# PowerHAT_1B1.net
KiCad netlist of a schematic drawn in Altium Designer
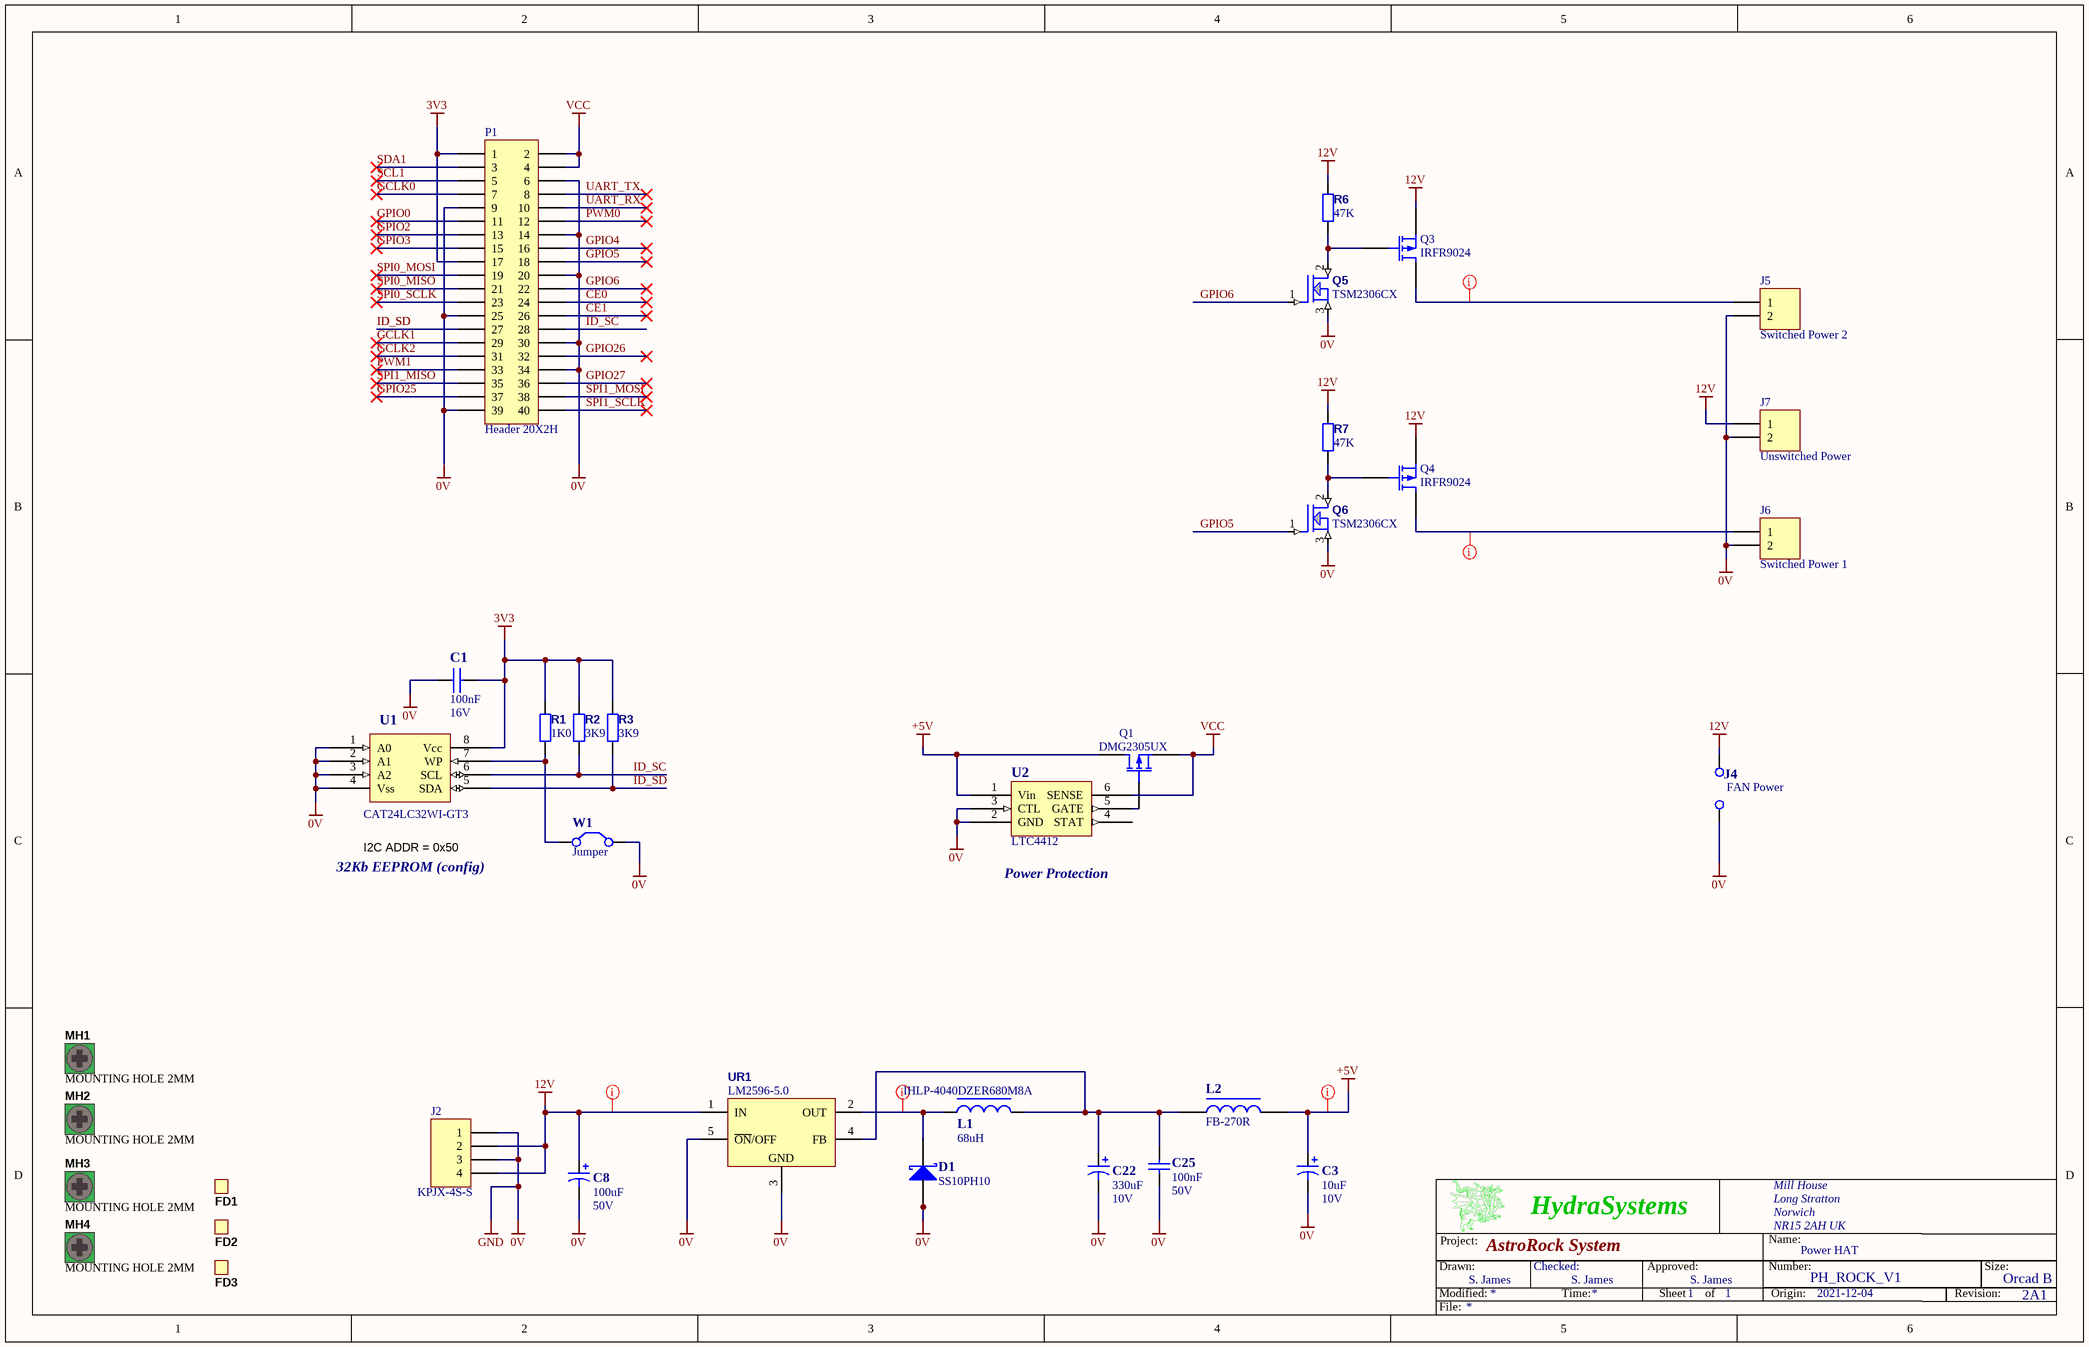
[diagram p0: PowerHAT_1B1.SchDoc]

(export (version "E")
  (design (tool "Eeschema 10.0.6"))
  (components
    (comp (ref "C1")
      (value "100nF")
      (footprint "0603_C")
      (description "MLCC 100nF 0402 X7R 16V")
      (fields (field (name "VOLTAGE") "16V"))
      (libsource (lib "*") (part "CAPACITOR NON-POL"))
    )
    (comp (ref "C3")
      (value "10uF")
      (footprint "1206")
      (description "Polarized Capacitor (Surface Mount)")
      (fields (field (name "VOLTAGE") "10V"))
      (libsource (lib "Miscellaneous Devices") (part "Cap Pol3"))
    )
    (comp (ref "C8")
      (value "100uF")
      (footprint "CASE H")
      (description "Polarized Capacitor (Surface Mount)")
      (fields (field (name "VOLTAGE") "50V"))
      (libsource (lib "Miscellaneous Devices") (part "Cap Pol3"))
    )
    (comp (ref "C22")
      (value "330uF")
      (footprint "2812")
      (description "Polarized Capacitor (Surface Mount)")
      (fields (field (name "VOLTAGE") "10V"))
      (libsource (lib "Miscellaneous Devices") (part "Cap Pol3"))
    )
    (comp (ref "C25")
      (value "100nF")
      (footprint "SM/R_0603")
      (description "Capacitor")
      (fields (field (name "VOLTAGE") "50V"))
      (libsource (lib "A1267-1A1") (part "Cap"))
    )
    (comp (ref "D1")
      (value "SS10PH10")
      (footprint "TO-277A")
      (description "Schottky Rectifier")
      (fields (field (name "MANUFACTURER") "Vishay"))
      (libsource (lib "BoatMonitor_2A1") (part "SS10PH"))
    )
    (comp (ref "FD1")
      (value "Fiducial")
      (footprint "Fiducial")
      (description "Registration Fiducial")
      (libsource (lib "Fiducial_1A1") (part "Fiducial"))
    )
    (comp (ref "FD2")
      (value "Fiducial")
      (footprint "Fiducial")
      (description "Registration Fiducial")
      (libsource (lib "Fiducial_1A1") (part "Fiducial"))
    )
    (comp (ref "FD3")
      (value "Fiducial")
      (footprint "Fiducial")
      (description "Registration Fiducial")
      (libsource (lib "Fiducial_1A1") (part "Fiducial"))
    )
    (comp (ref "J2")
      (value "KPJX-4S-S")
      (footprint "KPJX-4S-S")
      (description "Power 4-Pin")
      (fields (field (name "PUBLISHER") "Altium Limited"))
      (libsource (lib "Miscellaneous Connectors") (part "Header 4"))
    )
    (comp (ref "J4")
      (value "FAN Power")
      (footprint "CON2")
      (description "2 pads")
      (fields (field (name "PUBLISHER") "Altium Limited"))
      (libsource (lib "PowerHAT_1A1") (part "Pads"))
    )
    (comp (ref "J5")
      (value "Switched Power 2")
      (footprint "DCJ250-20")
      (description "Power Jack")
      (fields (field (name "PUBLISHER") "Altium Limited"))
      (libsource (lib "Miscellaneous Connectors") (part "Header 2"))
    )
    (comp (ref "J6")
      (value "Switched Power 1")
      (footprint "DCJ250-20")
      (description "Power Jack")
      (fields (field (name "PUBLISHER") "Altium Limited"))
      (libsource (lib "Miscellaneous Connectors") (part "Header 2"))
    )
    (comp (ref "J7")
      (value "Unswitched Power")
      (footprint "DCJ250-20")
      (description "Power Jack")
      (fields (field (name "PUBLISHER") "Altium Limited"))
      (libsource (lib "Miscellaneous Connectors") (part "Header 2"))
    )
    (comp (ref "L1")
      (value "68uH")
      (footprint "IHLP4040DZER")
      (description "Ferrite Inductor")
      (fields (field (name "MANUFACTURER") "Vishay") (field (name "PART NUMBER 68") "IHLP-4040DZER680M8A"))
      (libsource (lib "BoatMonitor_2A1") (part "Ferrite Inductor"))
    )
    (comp (ref "L2")
      (value "FB-270R")
      (footprint "2220")
      (description "Ferrite Bead")
      (fields (field (name "MANUFACTURER") "Wurth"))
      (libsource (lib "BoatMonitor_2A1") (part "Ferrite Bead"))
    )
    (comp (ref "MH1")
      (value "MOUNTING HOLE 2MM")
      (footprint "MOUNTING_HOLE_2MM")
      (description "Mounting Hole, M2 Screw, Plated, Square Pad")
      (libsource (lib "BoatMonitor_2A1") (part "MOUNTING_HOLE_2MM"))
    )
    (comp (ref "MH2")
      (value "MOUNTING HOLE 2MM")
      (footprint "MOUNTING_HOLE_2MM")
      (description "Mounting Hole, M2 Screw, Plated, Square Pad")
      (libsource (lib "BoatMonitor_2A1") (part "MOUNTING_HOLE_2MM"))
    )
    (comp (ref "MH3")
      (value "MOUNTING HOLE 2MM")
      (footprint "MOUNTING_HOLE_2MM")
      (description "Mounting Hole, M2 Screw, Plated, Square Pad")
      (libsource (lib "BoatMonitor_2A1") (part "MOUNTING_HOLE_2MM"))
    )
    (comp (ref "MH4")
      (value "MOUNTING HOLE 2MM")
      (footprint "MOUNTING_HOLE_2MM")
      (description "Mounting Hole, M2 Screw, Plated, Square Pad")
      (libsource (lib "BoatMonitor_2A1") (part "MOUNTING_HOLE_2MM"))
    )
    (comp (ref "P1")
      (value "Header 20X2H")
      (footprint "Header40 Invert")
      (description "Header, 20-Pin, Dual row, Right Angle")
      (fields (field (name "PUBLISHER") "Altium Limited"))
      (libsource (lib "Miscellaneous Connectors") (part "Header 20X2H"))
    )
    (comp (ref "Q1")
      (value "DMG2305UX")
      (footprint "DMG2305")
      (description "P-Channel MOSFET")
      (fields (field (name "PUBLISHER") "Altium Limited"))
      (libsource (lib "PowerHAT_1A1") (part "DMG2305UX"))
    )
    (comp (ref "Q3")
      (value "IRFR9024")
      (footprint "TO-252AA")
      (description "P-Channel MOSFET")
      (fields (field (name "PUBLISHER") "Altium Limited"))
      (libsource (lib "PowerHAT_1A1") (part "MOSFET-P"))
    )
    (comp (ref "Q4")
      (value "IRFR9024")
      (footprint "TO-252AA")
      (description "P-Channel MOSFET")
      (fields (field (name "PUBLISHER") "Altium Limited"))
      (libsource (lib "PowerHAT_1A1") (part "MOSFET-P"))
    )
    (comp (ref "Q5")
      (value "TSM2306CX")
      (footprint "FDV301N")
      (description "MOSFET, N Channel, 30 V, 3.5 A, 0.046 ohm, SOT-23")
      (fields (field (name "FULL PART NUMBER") "TSM2306CX RFG"))
      (libsource (lib "ESP32WIFI_1A1") (part "FDV301N"))
    )
    (comp (ref "Q6")
      (value "TSM2306CX")
      (footprint "FDV301N")
      (description "MOSFET, N Channel, 30 V, 3.5 A, 0.046 ohm, SOT-23")
      (fields (field (name "FULL PART NUMBER") "TSM2306CX RFG"))
      (libsource (lib "ESP32WIFI_1A1") (part "FDV301N"))
    )
    (comp (ref "R1")
      (value "1K0")
      (footprint "SM/R_0603")
      (description "Resistor")
      (fields (field (name "PUBLISHER") "Altium Limited"))
      (libsource (lib "PowerHAT_1A1") (part "Res2"))
    )
    (comp (ref "R2")
      (value "3K9")
      (footprint "SM/R_0603")
      (description "Resistor")
      (fields (field (name "PUBLISHER") "Altium Limited"))
      (libsource (lib "PowerHAT_1A1") (part "Res2"))
    )
    (comp (ref "R3")
      (value "3K9")
      (footprint "SM/R_0603")
      (description "Resistor")
      (fields (field (name "PUBLISHER") "Altium Limited"))
      (libsource (lib "PowerHAT_1A1") (part "Res2"))
    )
    (comp (ref "R6")
      (value "47K")
      (footprint "SM/R_0603")
      (description "Resistor")
      (fields (field (name "PUBLISHER") "Altium Limited"))
      (libsource (lib "PowerHAT_1A1") (part "Res2"))
    )
    (comp (ref "R7")
      (value "47K")
      (footprint "SM/R_0603")
      (description "Resistor")
      (fields (field (name "PUBLISHER") "Altium Limited"))
      (libsource (lib "PowerHAT_1A1") (part "Res2"))
    )
    (comp (ref "U1") (value "CAT24LC32WI-GT3") (footprint "SO-8") (libsource (lib "*") (part "24LC00")))
    (comp (ref "U2")
      (value "LTC4412")
      (footprint "SOT23-6_M")
      (libsource (lib "PowerHAT_1A1") (part "LTC4412"))
    )
    (comp (ref "UR1")
      (value "LM2596-5.0")
      (footprint "LM2596")
      (description "1000mA DC/DC Convertor, 3-pin SIP")
      (fields (field (name "PARTNUMBER") "TO-263"))
      (libsource (lib "BoatMonitor_2A1") (part "LM2596-ADJ"))
    )
    (comp (ref "W1")
      (value "Jumper")
      (footprint "Link2")
      (description "Jumper Wire")
      (fields (field (name "PUBLISHER") "Altium Limited"))
      (libsource (lib "HEE100") (part "Jumper"))
    )
  )
  (nets
    (net (code "1") (name "+5V") (class "Default")
      (node (ref "C3") (pin "1") (pinfunction "1_1") (pintype "passive"))
      (node (ref "L2") (pin "2") (pinfunction "2_2") (pintype "passive"))
      (node (ref "Q1") (pin "1") (pinfunction "D_1") (pintype "passive"))
      (node (ref "U2") (pin "1") (pinfunction "Vin_1") (pintype "power_in"))
    )
    (net (code "2") (name "/CE0") (class "Default")
      (node (ref "P1") (pin "24") (pinfunction "24_24") (pintype "passive+no_connect"))
    )
    (net (code "3") (name "/CE1") (class "Default")
      (node (ref "P1") (pin "26") (pinfunction "26_26") (pintype "passive+no_connect"))
    )
    (net (code "4") (name "/GCLK0") (class "Default")
      (node (ref "P1") (pin "7") (pinfunction "7_7") (pintype "passive+no_connect"))
    )
    (net (code "5") (name "/GCLK1") (class "Default")
      (node (ref "P1") (pin "29") (pinfunction "29_29") (pintype "passive+no_connect"))
    )
    (net (code "6") (name "/GCLK2") (class "Default")
      (node (ref "P1") (pin "31") (pinfunction "31_31") (pintype "passive+no_connect"))
    )
    (net (code "7") (name "/GPIO0") (class "Default")
      (node (ref "P1") (pin "11") (pinfunction "11_11") (pintype "passive+no_connect"))
    )
    (net (code "8") (name "/GPIO2") (class "Default")
      (node (ref "P1") (pin "13") (pinfunction "13_13") (pintype "passive+no_connect"))
    )
    (net (code "9") (name "/GPIO3") (class "Default")
      (node (ref "P1") (pin "15") (pinfunction "15_15") (pintype "passive+no_connect"))
    )
    (net (code "10") (name "/GPIO4") (class "Default")
      (node (ref "P1") (pin "16") (pinfunction "16_16") (pintype "passive+no_connect"))
    )
    (net (code "11") (name "/GPIO5") (class "Default")
      (node (ref "P1") (pin "18") (pinfunction "18_18") (pintype "passive"))
      (node (ref "Q6") (pin "1") (pinfunction "G_1") (pintype "input"))
    )
    (net (code "12") (name "/GPIO6") (class "Default")
      (node (ref "P1") (pin "22") (pinfunction "22_22") (pintype "passive"))
      (node (ref "Q5") (pin "1") (pinfunction "G_1") (pintype "input"))
    )
    (net (code "13") (name "/GPIO25") (class "Default")
      (node (ref "P1") (pin "37") (pinfunction "37_37") (pintype "passive+no_connect"))
    )
    (net (code "14") (name "/GPIO26") (class "Default")
      (node (ref "P1") (pin "32") (pinfunction "32_32") (pintype "passive+no_connect"))
    )
    (net (code "15") (name "/GPIO27") (class "Default")
      (node (ref "P1") (pin "36") (pinfunction "36_36") (pintype "passive+no_connect"))
    )
    (net (code "16") (name "/ID_SC") (class "Default")
      (node (ref "P1") (pin "28") (pinfunction "28_28") (pintype "passive"))
      (node (ref "R2") (pin "1") (pinfunction "1_1") (pintype "passive"))
      (node (ref "U1") (pin "6") (pinfunction "SCL_6") (pintype "bidirectional"))
    )
    (net (code "17") (name "/ID_SD") (class "Default")
      (node (ref "P1") (pin "27") (pinfunction "27_27") (pintype "passive"))
      (node (ref "R3") (pin "1") (pinfunction "1_1") (pintype "passive"))
      (node (ref "U1") (pin "5") (pinfunction "SDA_5") (pintype "bidirectional"))
    )
    (net (code "18") (name "/PWM0") (class "Default")
      (node (ref "P1") (pin "12") (pinfunction "12_12") (pintype "passive+no_connect"))
    )
    (net (code "19") (name "/PWM1") (class "Default")
      (node (ref "P1") (pin "33") (pinfunction "33_33") (pintype "passive+no_connect"))
    )
    (net (code "20") (name "/SCL1") (class "Default")
      (node (ref "P1") (pin "5") (pinfunction "5_5") (pintype "passive+no_connect"))
    )
    (net (code "21") (name "/SDA1") (class "Default")
      (node (ref "P1") (pin "3") (pinfunction "3_3") (pintype "passive+no_connect"))
    )
    (net (code "22") (name "/SPI0_MISO") (class "Default")
      (node (ref "P1") (pin "21") (pinfunction "21_21") (pintype "passive+no_connect"))
    )
    (net (code "23") (name "/SPI0_MOSI") (class "Default")
      (node (ref "P1") (pin "19") (pinfunction "19_19") (pintype "passive+no_connect"))
    )
    (net (code "24") (name "/SPI0_SCLK") (class "Default")
      (node (ref "P1") (pin "23") (pinfunction "23_23") (pintype "passive+no_connect"))
    )
    (net (code "25") (name "/SPI1_MISO") (class "Default")
      (node (ref "P1") (pin "35") (pinfunction "35_35") (pintype "passive+no_connect"))
    )
    (net (code "26") (name "/SPI1_MOSI") (class "Default")
      (node (ref "P1") (pin "38") (pinfunction "38_38") (pintype "passive+no_connect"))
    )
    (net (code "27") (name "/SPI1_SCLK") (class "Default")
      (node (ref "P1") (pin "40") (pinfunction "40_40") (pintype "passive+no_connect"))
    )
    (net (code "28") (name "/UART_RX") (class "Default")
      (node (ref "P1") (pin "10") (pinfunction "10_10") (pintype "passive+no_connect"))
    )
    (net (code "29") (name "/UART_TX") (class "Default")
      (node (ref "P1") (pin "8") (pinfunction "8_8") (pintype "passive+no_connect"))
    )
    (net (code "30") (name "0V") (class "Default")
      (node (ref "C1") (pin "1") (pinfunction "1_1") (pintype "passive"))
      (node (ref "C22") (pin "2") (pinfunction "2_2") (pintype "passive"))
      (node (ref "C25") (pin "1") (pinfunction "1_1") (pintype "passive"))
      (node (ref "C3") (pin "2") (pinfunction "2_2") (pintype "passive"))
      (node (ref "C8") (pin "2") (pinfunction "2_2") (pintype "passive"))
      (node (ref "D1") (pin "2") (pinfunction "A1_2") (pintype "passive"))
      (node (ref "D1") (pin "3") (pinfunction "A2_3") (pintype "passive"))
      (node (ref "J2") (pin "1") (pinfunction "1_1") (pintype "passive"))
      (node (ref "J2") (pin "3") (pinfunction "3_3") (pintype "passive"))
      (node (ref "J4") (pin "1") (pinfunction "C1_1") (pintype "passive"))
      (node (ref "J5") (pin "2") (pinfunction "2_2") (pintype "passive"))
      (node (ref "J6") (pin "2") (pinfunction "2_2") (pintype "passive"))
      (node (ref "J7") (pin "2") (pinfunction "2_2") (pintype "passive"))
      (node (ref "P1") (pin "14") (pinfunction "14_14") (pintype "passive"))
      (node (ref "P1") (pin "20") (pinfunction "20_20") (pintype "passive"))
      (node (ref "P1") (pin "25") (pinfunction "25_25") (pintype "passive"))
      (node (ref "P1") (pin "30") (pinfunction "30_30") (pintype "passive"))
      (node (ref "P1") (pin "34") (pinfunction "34_34") (pintype "passive"))
      (node (ref "P1") (pin "39") (pinfunction "39_39") (pintype "passive"))
      (node (ref "P1") (pin "6") (pinfunction "6_6") (pintype "passive"))
      (node (ref "P1") (pin "9") (pinfunction "9_9") (pintype "passive"))
      (node (ref "Q5") (pin "3") (pinfunction "S_3") (pintype "input"))
      (node (ref "Q6") (pin "3") (pinfunction "S_3") (pintype "input"))
      (node (ref "U1") (pin "1") (pinfunction "A0_1") (pintype "input"))
      (node (ref "U1") (pin "2") (pinfunction "A1_2") (pintype "input"))
      (node (ref "U1") (pin "3") (pinfunction "A2_3") (pintype "input"))
      (node (ref "U1") (pin "4") (pinfunction "Vss_4") (pintype "power_in"))
      (node (ref "U2") (pin "2") (pinfunction "GND_2") (pintype "power_in"))
      (node (ref "U2") (pin "3") (pinfunction "CTL_3") (pintype "input"))
      (node (ref "UR1") (pin "3") (pinfunction "GND_3") (pintype "power_in"))
      (node (ref "UR1") (pin "5") (pinfunction "~{ON}/OFF_5") (pintype "power_in"))
      (node (ref "W1") (pin "2") (pinfunction "C2_2") (pintype "passive"))
    )
    (net (code "31") (name "3V3") (class "Default")
      (node (ref "C1") (pin "2") (pinfunction "2_2") (pintype "passive"))
      (node (ref "P1") (pin "1") (pinfunction "1_1") (pintype "passive"))
      (node (ref "P1") (pin "17") (pinfunction "17_17") (pintype "passive"))
      (node (ref "R1") (pin "2") (pinfunction "2_2") (pintype "passive"))
      (node (ref "R2") (pin "2") (pinfunction "2_2") (pintype "passive"))
      (node (ref "R3") (pin "2") (pinfunction "2_2") (pintype "passive"))
      (node (ref "U1") (pin "8") (pinfunction "Vcc_8") (pintype "power_in"))
    )
    (net (code "32") (name "12V") (class "Default")
      (node (ref "C8") (pin "1") (pinfunction "1_1") (pintype "passive"))
      (node (ref "J2") (pin "2") (pinfunction "2_2") (pintype "passive"))
      (node (ref "J2") (pin "4") (pinfunction "4_4") (pintype "passive"))
      (node (ref "J4") (pin "2") (pinfunction "C2_2") (pintype "passive"))
      (node (ref "J7") (pin "1") (pinfunction "1_1") (pintype "passive"))
      (node (ref "Q3") (pin "3") (pinfunction "S_3") (pintype "passive"))
      (node (ref "Q4") (pin "3") (pinfunction "S_3") (pintype "passive"))
      (node (ref "R6") (pin "2") (pinfunction "2_2") (pintype "passive"))
      (node (ref "R7") (pin "2") (pinfunction "2_2") (pintype "passive"))
      (node (ref "UR1") (pin "1") (pinfunction "IN_1") (pintype "power_in"))
    )
    (net (code "33") (name "Net-(D1-K)") (class "Default")
      (node (ref "D1") (pin "1") (pinfunction "K_1") (pintype "passive"))
      (node (ref "L1") (pin "1") (pinfunction "1_1") (pintype "passive"))
      (node (ref "UR1") (pin "2") (pinfunction "OUT_2") (pintype "power_in"))
    )
    (net (code "34") (name "Net-(Q1-G)") (class "Default")
      (node (ref "Q1") (pin "2") (pinfunction "G_2") (pintype "passive"))
      (node (ref "U2") (pin "5") (pinfunction "GATE_5") (pintype "output"))
    )
    (net (code "35") (name "Net-(Q3-D)") (class "Default")
      (node (ref "J5") (pin "1") (pinfunction "1_1") (pintype "passive"))
      (node (ref "Q3") (pin "1") (pinfunction "D_1") (pintype "passive"))
    )
    (net (code "36") (name "Net-(Q3-G)") (class "Default")
      (node (ref "Q3") (pin "2") (pinfunction "G_2") (pintype "passive"))
      (node (ref "Q5") (pin "2") (pinfunction "D_2") (pintype "input"))
      (node (ref "R6") (pin "1") (pinfunction "1_1") (pintype "passive"))
    )
    (net (code "37") (name "Net-(Q4-D)") (class "Default")
      (node (ref "J6") (pin "1") (pinfunction "1_1") (pintype "passive"))
      (node (ref "Q4") (pin "1") (pinfunction "D_1") (pintype "passive"))
    )
    (net (code "38") (name "Net-(Q4-G)") (class "Default")
      (node (ref "Q4") (pin "2") (pinfunction "G_2") (pintype "passive"))
      (node (ref "Q6") (pin "2") (pinfunction "D_2") (pintype "input"))
      (node (ref "R7") (pin "1") (pinfunction "1_1") (pintype "passive"))
    )
    (net (code "39") (name "Net-(U1-WP)") (class "Default")
      (node (ref "R1") (pin "1") (pinfunction "1_1") (pintype "passive"))
      (node (ref "U1") (pin "7") (pinfunction "WP_7") (pintype "input"))
      (node (ref "W1") (pin "1") (pinfunction "C1_1") (pintype "passive"))
    )
    (net (code "40") (name "Net-(UR1-FB)") (class "Default")
      (node (ref "C22") (pin "1") (pinfunction "1_1") (pintype "passive"))
      (node (ref "C25") (pin "2") (pinfunction "2_2") (pintype "passive"))
      (node (ref "L1") (pin "2") (pinfunction "2_2") (pintype "passive"))
      (node (ref "L2") (pin "1") (pinfunction "1_1") (pintype "passive"))
      (node (ref "UR1") (pin "4") (pinfunction "FB_4") (pintype "power_in"))
    )
    (net (code "41") (name "VCC") (class "Default")
      (node (ref "P1") (pin "2") (pinfunction "2_2") (pintype "passive"))
      (node (ref "P1") (pin "4") (pinfunction "4_4") (pintype "passive"))
      (node (ref "Q1") (pin "3") (pinfunction "S_3") (pintype "passive"))
      (node (ref "U2") (pin "6") (pinfunction "SENSE_6") (pintype "power_in"))
    )
    (net (code "42") (name "unconnected-(MH1-PadMOUNT)") (class "Default")
      (node (ref "MH1") (pin "MOUNT") (pinfunction "MOUNT_MOUNT") (pintype "passive"))
    )
    (net (code "43") (name "unconnected-(MH2-PadMOUNT)") (class "Default")
      (node (ref "MH2") (pin "MOUNT") (pinfunction "MOUNT_MOUNT") (pintype "passive"))
    )
    (net (code "44") (name "unconnected-(MH3-PadMOUNT)") (class "Default")
      (node (ref "MH3") (pin "MOUNT") (pinfunction "MOUNT_MOUNT") (pintype "passive"))
    )
    (net (code "45") (name "unconnected-(MH4-PadMOUNT)") (class "Default")
      (node (ref "MH4") (pin "MOUNT") (pinfunction "MOUNT_MOUNT") (pintype "passive"))
    )
    (net (code "46") (name "unconnected-(U2-STAT-Pad4)") (class "Default")
      (node (ref "U2") (pin "4") (pinfunction "STAT_4") (pintype "output"))
    )
  )
)
